# Inverter.net
KiCad netlist of a schematic drawn in EAGLE
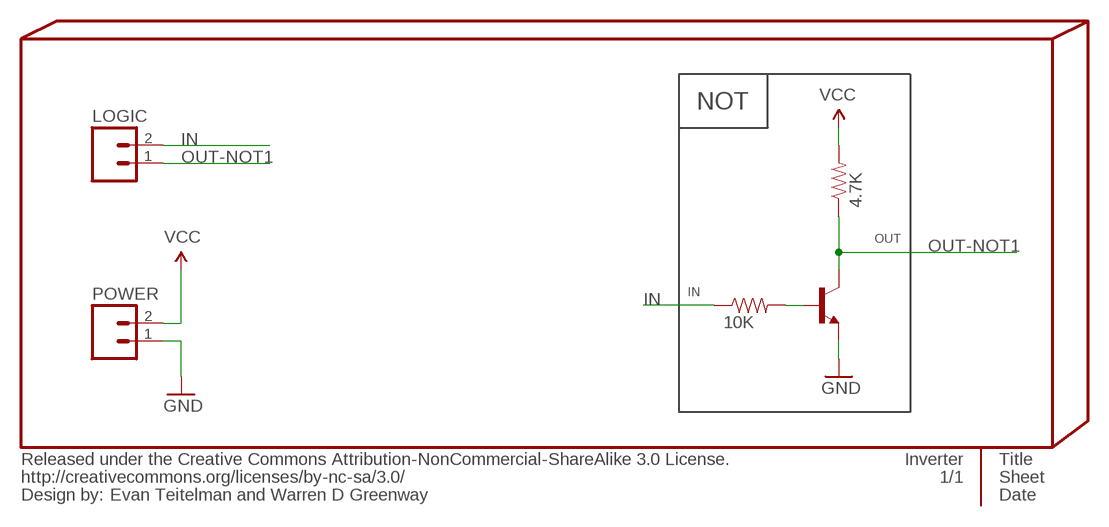
[diagram p0: schematic, sheet 1]

(export (version "E")
  (design (tool "Eeschema 10.0.6"))
  (components
    (comp (ref "INFO4")
      (value "Evan Teitelman and Warren D Greenway")
      (footprint "eagle-import:%CC-NC-SA")
      (libsource (lib "eagle-import") (part "%CC-NC-SA"))
    )
    (comp (ref "LOGIC")
      (value "M02PTH")
      (footprint "eagle-import:1X02")
      (libsource (lib "eagle-import") (part "M02PTH"))
    )
    (comp (ref "POWER")
      (value "M02PTH")
      (footprint "eagle-import:1X02")
      (libsource (lib "eagle-import") (part "M02PTH"))
    )
    (comp (ref "PUR-NOT1")
      (value "4.7K")
      (footprint "eagle-import:0402-RES")
      (libsource (lib "eagle-import") (part "RESISTOR0402-RES"))
    )
    (comp (ref "Q-NOT1")
      (value "TRANSISTOR_NPNSOT23")
      (footprint "eagle-import:SOT23")
      (libsource (lib "eagle-import") (part "TRANSISTOR_NPNSOT23"))
    )
    (comp (ref "R-NOT1")
      (value "10K")
      (footprint "eagle-import:0402-RES")
      (libsource (lib "eagle-import") (part "RESISTOR0402-RES"))
    )
  )
  (nets
    (net (code "1") (name "/IN") (class "Default")
      (node (ref "LOGIC") (pin "2") (pinfunction "2_2") (pintype "passive"))
      (node (ref "R-NOT1") (pin "1") (pinfunction "1_1") (pintype "passive"))
    )
    (net (code "2") (name "/OUT-NOT1") (class "Default")
      (node (ref "LOGIC") (pin "1") (pinfunction "1_1") (pintype "passive"))
      (node (ref "PUR-NOT1") (pin "1") (pinfunction "1_1") (pintype "passive"))
      (node (ref "Q-NOT1") (pin "3") (pinfunction "C_3") (pintype "passive"))
    )
    (net (code "3") (name "@GND") (class "Default")
      (node (ref "POWER") (pin "1") (pinfunction "1_1") (pintype "passive"))
      (node (ref "Q-NOT1") (pin "2") (pinfunction "E_2") (pintype "passive"))
    )
    (net (code "4") (name "@VCC") (class "Default")
      (node (ref "POWER") (pin "2") (pinfunction "2_2") (pintype "passive"))
      (node (ref "PUR-NOT1") (pin "2") (pinfunction "2_2") (pintype "passive"))
    )
    (net (code "5") (name "Net-(Q-NOT1-B)") (class "Default")
      (node (ref "Q-NOT1") (pin "1") (pinfunction "B_1") (pintype "passive"))
      (node (ref "R-NOT1") (pin "2") (pinfunction "2_2") (pintype "passive"))
    )
  )
)
